# leo_IMU.net
KiCad netlist of a schematic drawn in Altium Designer
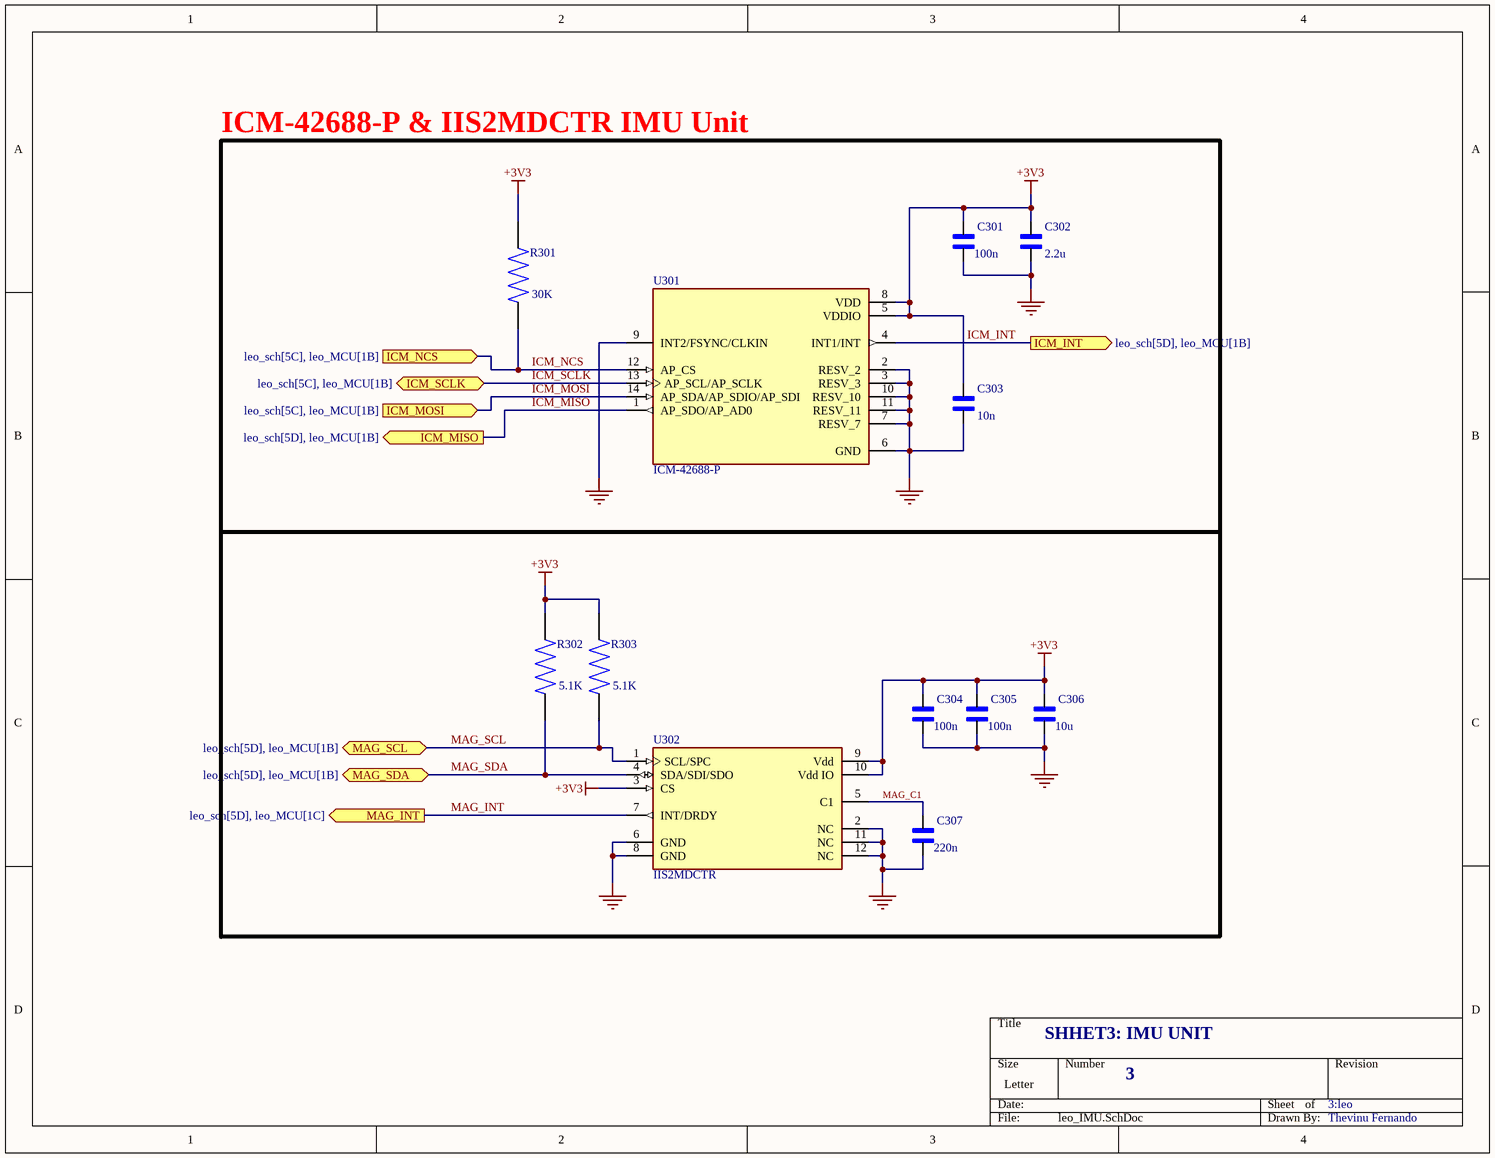
[diagram p0: leo_IMU.SchDoc]

(export (version "E")
  (design (tool "Eeschema 10.0.6"))
  (components
    (comp (ref "C301")
      (value "100n")
      (footprint "CAP_0402")
      (description "Ceramic Capacitor X7R 0402 (1005 Metric)")
      (fields (field (name "MF") "Samsung") (field (name "MP") "CL05B104KO5NNNC"))
      (libsource (lib "leo_schlib") (part "CAP_0402"))
    )
    (comp (ref "C302")
      (value "2.2u")
      (footprint "CAP_0603")
      (description "Ceramic Capacitor X5R 0603 (1608 Metric)")
      (fields (field (name "MF") "Samsung Electro-Mechanics") (field (name "MP") "CL10A475KO8NNNC"))
      (libsource (lib "leo_schlib") (part "CAP_0603"))
    )
    (comp (ref "C303")
      (value "10n")
      (footprint "CAP_0402")
      (description "Ceramic Capacitor X7R 0402 (1005 Metric)")
      (fields (field (name "MF") "Samsung") (field (name "MP") "CL05B104KO5NNNC"))
      (libsource (lib "leo_schlib") (part "CAP_0402"))
    )
    (comp (ref "C304")
      (value "100n")
      (footprint "CAP_0402")
      (description "Ceramic Capacitor X7R 0402 (1005 Metric)")
      (fields (field (name "MF") "Samsung") (field (name "MP") "CL05B104KO5NNNC"))
      (libsource (lib "leo_schlib") (part "CAP_0402"))
    )
    (comp (ref "C305")
      (value "100n")
      (footprint "CAP_0402")
      (description "Ceramic Capacitor X7R 0402 (1005 Metric)")
      (fields (field (name "MF") "Samsung") (field (name "MP") "CL05B104KO5NNNC"))
      (libsource (lib "leo_schlib") (part "CAP_0402"))
    )
    (comp (ref "C306")
      (value "10u")
      (footprint "CAP_0805")
      (description "Ceramic Capacitor X7R 0805 (2012 Metric)")
      (fields (field (name "MF") "Samsung Electro-Mechanics") (field (name "MP") "CL21B106KOQNNNE"))
      (libsource (lib "leo_schlib") (part "CAP_0805"))
    )
    (comp (ref "C307")
      (value "220n")
      (footprint "CAP_0402")
      (description "Ceramic Capacitor X7R 0402 (1005 Metric)")
      (fields (field (name "MF") "Samsung") (field (name "MP") "CL05B104KO5NNNC"))
      (libsource (lib "leo_schlib") (part "CAP_0402"))
    )
    (comp (ref "R301")
      (value "30K")
      (footprint "RES_0402")
      (description "Chip Resistor 0402 (1005 Metric) Automotive AEC-Q200 Thick Film")
      (fields (field (name "MF") "Panasonic") (field (name "MP") "ERJ-2RKF1002X"))
      (libsource (lib "leo_schlib") (part "RES_0402"))
    )
    (comp (ref "R302")
      (value "5.1K")
      (footprint "RES_0402")
      (description "Chip Resistor 0402 (1005 Metric) Automotive AEC-Q200 Thick Film")
      (fields (field (name "MF") "Panasonic") (field (name "MP") "ERJ-2RKF1002X"))
      (libsource (lib "leo_schlib") (part "RES_0402"))
    )
    (comp (ref "R303")
      (value "5.1K")
      (footprint "RES_0402")
      (description "Chip Resistor 0402 (1005 Metric) Automotive AEC-Q200 Thick Film")
      (fields (field (name "MF") "Panasonic") (field (name "MP") "ERJ-2RKF1002X"))
      (libsource (lib "leo_schlib") (part "RES_0402"))
    )
    (comp (ref "U301")
      (value "ICM-42688-P")
      (footprint "PQFN50P300X250X97-14N")
      (description "Accelerometer, Gyroscope, 6 Axis Sensor Output")
      (libsource (lib "leo_schlib") (part "ICM-42688-P"))
    )
    (comp (ref "U302")
      (value "IIS2MDCTR")
      (footprint "FP-LGA-12-DM00170568-MFG")
      (description "High-accuracy, ultra-low-power, 3-axis digital output magnetometer")
      (libsource (lib "leo_schlib") (part "IIS2MDCTR"))
    )
  )
  (nets
    (net (code "1") (name "+3V3") (class "Default")
      (node (ref "C301") (pin "2") (pinfunction "2_2") (pintype "passive"))
      (node (ref "C302") (pin "2") (pinfunction "2_2") (pintype "passive"))
      (node (ref "C303") (pin "2") (pinfunction "2_2") (pintype "passive"))
      (node (ref "C304") (pin "2") (pinfunction "2_2") (pintype "passive"))
      (node (ref "C305") (pin "2") (pinfunction "2_2") (pintype "passive"))
      (node (ref "C306") (pin "1") (pinfunction "1_1") (pintype "passive"))
      (node (ref "R301") (pin "2") (pinfunction "2_2") (pintype "passive"))
      (node (ref "R302") (pin "2") (pinfunction "2_2") (pintype "passive"))
      (node (ref "R303") (pin "2") (pinfunction "2_2") (pintype "passive"))
      (node (ref "U301") (pin "5") (pinfunction "VDDIO_5") (pintype "power_in"))
      (node (ref "U301") (pin "8") (pinfunction "VDD_8") (pintype "power_in"))
      (node (ref "U302") (pin "10") (pinfunction "Vdd_IO_10") (pintype "power_in"))
      (node (ref "U302") (pin "3") (pinfunction "CS_3") (pintype "input"))
      (node (ref "U302") (pin "9") (pinfunction "Vdd_9") (pintype "power_in"))
    )
    (net (code "2") (name "/ICM_INT") (class "Default")
      (node (ref "U301") (pin "4") (pinfunction "INT1/INT_4") (pintype "output"))
    )
    (net (code "3") (name "/ICM_MISO") (class "Default")
      (node (ref "U301") (pin "1") (pinfunction "AP_SDO/AP_AD0_1") (pintype "output"))
    )
    (net (code "4") (name "/ICM_MOSI") (class "Default")
      (node (ref "U301") (pin "14") (pinfunction "AP_SDA/AP_SDIO/AP_SDI_14") (pintype "input"))
    )
    (net (code "5") (name "/ICM_NCS") (class "Default")
      (node (ref "R301") (pin "1") (pinfunction "1_1") (pintype "passive"))
      (node (ref "U301") (pin "12") (pinfunction "AP_CS_12") (pintype "input"))
    )
    (net (code "6") (name "/ICM_SCLK") (class "Default")
      (node (ref "U301") (pin "13") (pinfunction "AP_SCL/AP_SCLK_13") (pintype "input"))
    )
    (net (code "7") (name "/MAG_C1") (class "Default")
      (node (ref "C307") (pin "2") (pinfunction "2_2") (pintype "passive"))
      (node (ref "U302") (pin "5") (pinfunction "C1_5") (pintype "passive"))
    )
    (net (code "8") (name "/MAG_INT") (class "Default")
      (node (ref "U302") (pin "7") (pinfunction "INT/DRDY_7") (pintype "output"))
    )
    (net (code "9") (name "/MAG_SCL") (class "Default")
      (node (ref "R303") (pin "1") (pinfunction "1_1") (pintype "passive"))
      (node (ref "U302") (pin "1") (pinfunction "SCL/SPC_1") (pintype "input"))
    )
    (net (code "10") (name "/MAG_SDA") (class "Default")
      (node (ref "R302") (pin "1") (pinfunction "1_1") (pintype "passive"))
      (node (ref "U302") (pin "4") (pinfunction "SDA/SDI/SDO_4") (pintype "bidirectional"))
    )
    (net (code "11") (name "GND") (class "Default")
      (node (ref "C301") (pin "1") (pinfunction "1_1") (pintype "passive"))
      (node (ref "C302") (pin "1") (pinfunction "1_1") (pintype "passive"))
      (node (ref "C303") (pin "1") (pinfunction "1_1") (pintype "passive"))
      (node (ref "C304") (pin "1") (pinfunction "1_1") (pintype "passive"))
      (node (ref "C305") (pin "1") (pinfunction "1_1") (pintype "passive"))
      (node (ref "C306") (pin "2") (pinfunction "2_2") (pintype "passive"))
      (node (ref "C307") (pin "1") (pinfunction "1_1") (pintype "passive"))
      (node (ref "U301") (pin "10") (pinfunction "RESV_10_10") (pintype "passive"))
      (node (ref "U301") (pin "11") (pinfunction "RESV_11_11") (pintype "passive"))
      (node (ref "U301") (pin "2") (pinfunction "RESV_2_2") (pintype "passive"))
      (node (ref "U301") (pin "3") (pinfunction "RESV_3_3") (pintype "passive"))
      (node (ref "U301") (pin "6") (pinfunction "GND_6") (pintype "power_in"))
      (node (ref "U301") (pin "7") (pinfunction "RESV_7_7") (pintype "passive"))
      (node (ref "U301") (pin "9") (pinfunction "INT2/FSYNC/CLKIN_9") (pintype "passive"))
      (node (ref "U302") (pin "11") (pinfunction "NC_11") (pintype "passive"))
      (node (ref "U302") (pin "12") (pinfunction "NC_12") (pintype "passive"))
      (node (ref "U302") (pin "2") (pinfunction "NC_2") (pintype "passive"))
      (node (ref "U302") (pin "6") (pinfunction "GND_6") (pintype "power_in"))
      (node (ref "U302") (pin "8") (pinfunction "GND_8") (pintype "power_in"))
    )
  )
)
